# STM32F405RGT6.net
KiCad netlist of a schematic drawn in EAGLE
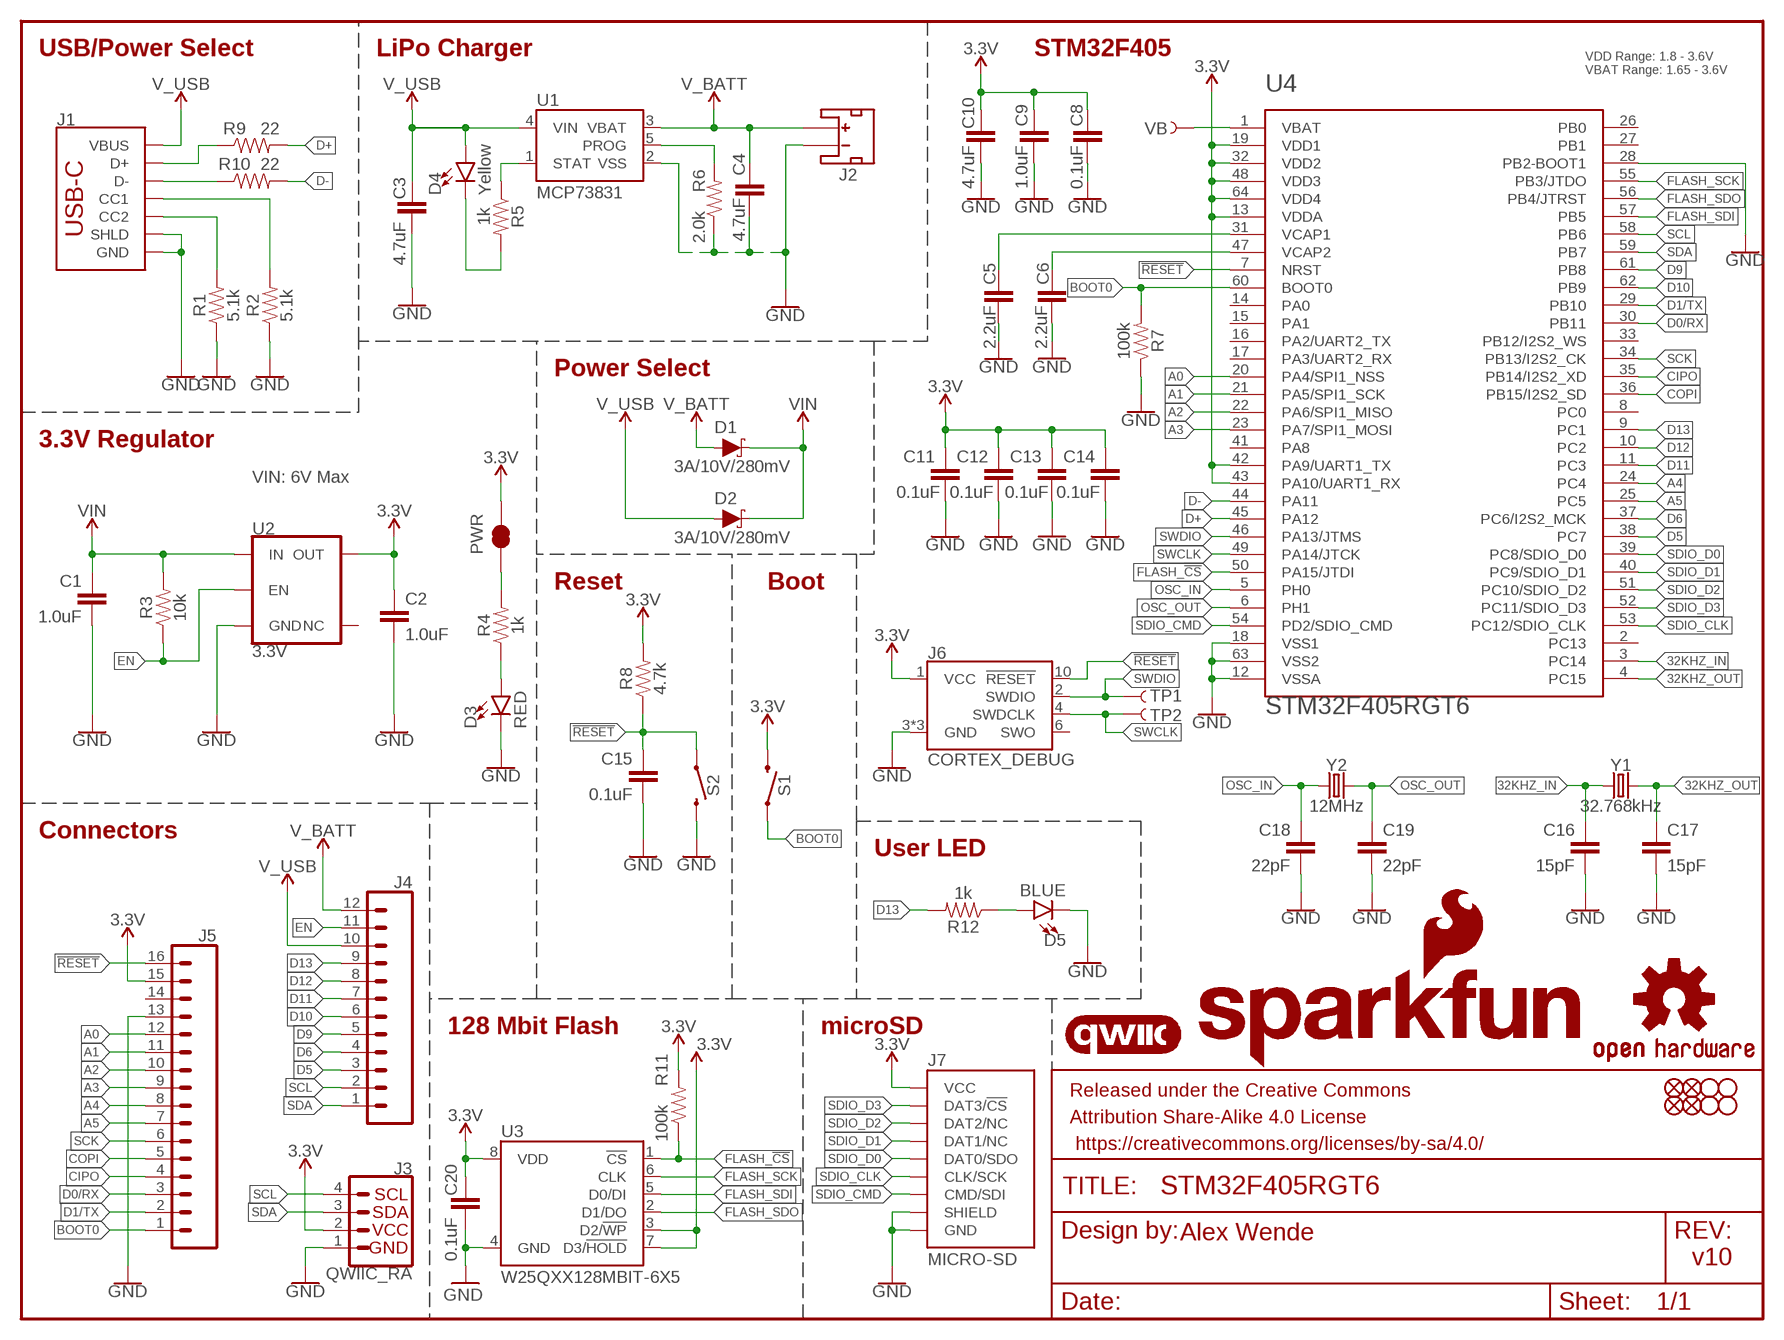
[diagram p0: schematic, sheet 1]

(export (version "E")
  (design (tool "Eeschema 10.0.6"))
  (components
    (comp (ref "C1")
      (value "1.0uF")
      (footprint "eagle-import:0402-TIGHT")
      (libsource (lib "eagle-import") (part "1.0UF-0402T-16V-10%"))
    )
    (comp (ref "C2")
      (value "1.0uF")
      (footprint "eagle-import:0402-TIGHT")
      (libsource (lib "eagle-import") (part "1.0UF-0402T-16V-10%"))
    )
    (comp (ref "C3")
      (value "4.7uF")
      (footprint "eagle-import:0402-TIGHT")
      (libsource (lib "eagle-import") (part "4.7UF-0402_TIGHT-6.3V-20%-X5R"))
    )
    (comp (ref "C4")
      (value "4.7uF")
      (footprint "eagle-import:0402-TIGHT")
      (libsource (lib "eagle-import") (part "4.7UF-0402_TIGHT-6.3V-20%-X5R"))
    )
    (comp (ref "C5")
      (value "2.2uF")
      (footprint "eagle-import:0402-TIGHT")
      (libsource (lib "eagle-import") (part "2.2UF-0402_TIGHT-10V-10%-X5R"))
    )
    (comp (ref "C6")
      (value "2.2uF")
      (footprint "eagle-import:0402-TIGHT")
      (libsource (lib "eagle-import") (part "2.2UF-0402_TIGHT-10V-10%-X5R"))
    )
    (comp (ref "C8")
      (value "0.1uF")
      (footprint "eagle-import:0402-TIGHT")
      (libsource (lib "eagle-import") (part "0.1UF-0402T-10V-10%-X7R"))
    )
    (comp (ref "C9")
      (value "1.0uF")
      (footprint "eagle-import:0402-TIGHT")
      (libsource (lib "eagle-import") (part "1.0UF-0402T-16V-10%"))
    )
    (comp (ref "C10")
      (value "4.7uF")
      (footprint "eagle-import:0402-TIGHT")
      (libsource (lib "eagle-import") (part "4.7UF-0402_TIGHT-6.3V-20%-X5R"))
    )
    (comp (ref "C11")
      (value "0.1uF")
      (footprint "eagle-import:0402-TIGHT")
      (libsource (lib "eagle-import") (part "0.1UF-0402T-10V-10%-X7R"))
    )
    (comp (ref "C12")
      (value "0.1uF")
      (footprint "eagle-import:0402-TIGHT")
      (libsource (lib "eagle-import") (part "0.1UF-0402T-10V-10%-X7R"))
    )
    (comp (ref "C13")
      (value "0.1uF")
      (footprint "eagle-import:0402-TIGHT")
      (libsource (lib "eagle-import") (part "0.1UF-0402T-10V-10%-X7R"))
    )
    (comp (ref "C14")
      (value "0.1uF")
      (footprint "eagle-import:0402-TIGHT")
      (libsource (lib "eagle-import") (part "0.1UF-0402T-10V-10%-X7R"))
    )
    (comp (ref "C15")
      (value "0.1uF")
      (footprint "eagle-import:0402-TIGHT")
      (libsource (lib "eagle-import") (part "0.1UF-0402T-10V-10%-X7R"))
    )
    (comp (ref "C16")
      (value "15pF")
      (footprint "eagle-import:0402-TIGHT")
      (libsource (lib "eagle-import") (part "15PF-0402T-50V-5%"))
    )
    (comp (ref "C17")
      (value "15pF")
      (footprint "eagle-import:0402-TIGHT")
      (libsource (lib "eagle-import") (part "15PF-0402T-50V-5%"))
    )
    (comp (ref "C18")
      (value "22pF")
      (footprint "eagle-import:0402-TIGHT")
      (libsource (lib "eagle-import") (part "22PF-0402T-16V-10%"))
    )
    (comp (ref "C19")
      (value "22pF")
      (footprint "eagle-import:0402-TIGHT")
      (libsource (lib "eagle-import") (part "22PF-0402T-16V-10%"))
    )
    (comp (ref "C20")
      (value "0.1uF")
      (footprint "eagle-import:0402-TIGHT")
      (libsource (lib "eagle-import") (part "0.1UF-0402T-10V-10%-X7R"))
    )
    (comp (ref "D1")
      (value "3A/10V/280mV")
      (footprint "eagle-import:SOD-323")
      (libsource (lib "eagle-import") (part "DIODE-SCHOTTKY-BAT60A"))
    )
    (comp (ref "D2")
      (value "3A/10V/280mV")
      (footprint "eagle-import:SOD-323")
      (libsource (lib "eagle-import") (part "DIODE-SCHOTTKY-BAT60A"))
    )
    (comp (ref "D3")
      (value "RED")
      (footprint "eagle-import:LED-0603")
      (libsource (lib "eagle-import") (part "LED-RED0603"))
    )
    (comp (ref "D4")
      (value "Yellow")
      (footprint "eagle-import:LED-0603")
      (libsource (lib "eagle-import") (part "LED-YELLOW0603"))
    )
    (comp (ref "D5")
      (value "BLUE")
      (footprint "eagle-import:LED-0603")
      (libsource (lib "eagle-import") (part "LED-BLUE0603"))
    )
    (comp (ref "FD1")
      (value "FIDUCIALUFIDUCIAL")
      (footprint "eagle-import:FIDUCIAL-MICRO")
      (libsource (lib "eagle-import") (part "FIDUCIALUFIDUCIAL"))
    )
    (comp (ref "FD2")
      (value "FIDUCIALUFIDUCIAL")
      (footprint "eagle-import:FIDUCIAL-MICRO")
      (libsource (lib "eagle-import") (part "FIDUCIALUFIDUCIAL"))
    )
    (comp (ref "FD3")
      (value "FIDUCIALUFIDUCIAL")
      (footprint "eagle-import:FIDUCIAL-MICRO")
      (libsource (lib "eagle-import") (part "FIDUCIALUFIDUCIAL"))
    )
    (comp (ref "FD4")
      (value "FIDUCIALUFIDUCIAL")
      (footprint "eagle-import:FIDUCIAL-MICRO")
      (libsource (lib "eagle-import") (part "FIDUCIALUFIDUCIAL"))
    )
    (comp (ref "FRAME1")
      (value "FRAME-LETTER")
      (footprint "eagle-import:CREATIVE_COMMONS")
      (libsource (lib "eagle-import") (part "FRAME-LETTER"))
    )
    (comp (ref "H1")
      (value "STAND-OFFTIGHT")
      (footprint "eagle-import:STAND-OFF-TIGHT")
      (libsource (lib "eagle-import") (part "STAND-OFFTIGHT"))
    )
    (comp (ref "H2")
      (value "STAND-OFFTIGHT")
      (footprint "eagle-import:STAND-OFF-TIGHT")
      (libsource (lib "eagle-import") (part "STAND-OFFTIGHT"))
    )
    (comp (ref "H3")
      (value "STAND-OFFTIGHT")
      (footprint "eagle-import:STAND-OFF-TIGHT")
      (libsource (lib "eagle-import") (part "STAND-OFFTIGHT"))
    )
    (comp (ref "H4")
      (value "STAND-OFFTIGHT")
      (footprint "eagle-import:STAND-OFF-TIGHT")
      (libsource (lib "eagle-import") (part "STAND-OFFTIGHT"))
    )
    (comp (ref "J1")
      (value "USB_C_2-LAYER_PADS")
      (footprint "eagle-import:USB-C-16P-2LAYER-PADS")
      (libsource (lib "eagle-import") (part "USB_C_2-LAYER_PADS"))
    )
    (comp (ref "J2")
      (value "JST_2MM_MALE")
      (footprint "eagle-import:JST-2-SMD")
      (libsource (lib "eagle-import") (part "JST_2MM_MALE"))
    )
    (comp (ref "J3")
      (value "QWIIC_RA")
      (footprint "eagle-import:JST04_1MM_RA")
      (libsource (lib "eagle-import") (part "QWIIC_CONNECTORJS-1MM"))
    )
    (comp (ref "J4")
      (value "CONN_12SM_SQ_NO_SILK")
      (footprint "eagle-import:1X12_SM_SQ_NOSILK")
      (libsource (lib "eagle-import") (part "CONN_12SM_SQ_NO_SILK"))
    )
    (comp (ref "J5")
      (value "CONN_161X16_SM_SQ_NOSILK")
      (footprint "eagle-import:1X16_SM_SQ_NOSILK")
      (libsource (lib "eagle-import") (part "CONN_161X16_SM_SQ_NOSILK"))
    )
    (comp (ref "J6")
      (value "CORTEX_DEBUG")
      (footprint "eagle-import:2X5-PTH-1.27MM-NO_SILK")
      (libsource (lib "eagle-import") (part "CORTEX_JTAG_DEBUG_MINIMUM_PTH_NS"))
    )
    (comp (ref "J7")
      (value "MICRO-SD")
      (footprint "eagle-import:MICRO-SD-SOCKET")
      (libsource (lib "eagle-import") (part "MICRO-SD-SDIOPUSH-PUSH"))
    )
    (comp (ref "LOGO1")
      (value "QWIIC_LOGO_5MM")
      (footprint "eagle-import:QWIIC_5MM")
      (libsource (lib "eagle-import") (part "QWIIC_LOGO_5MM"))
    )
    (comp (ref "LOGO2")
      (value "SFE_LOGO_NAME_FLAME.1_INCH")
      (footprint "eagle-import:SFE_LOGO_NAME_FLAME_.1")
      (libsource (lib "eagle-import") (part "SFE_LOGO_NAME_FLAME.1_INCH"))
    )
    (comp (ref "LOGO3")
      (value "OSHW-LOGOS")
      (footprint "eagle-import:OSHW-LOGO-S")
      (libsource (lib "eagle-import") (part "OSHW-LOGOS"))
    )
    (comp (ref "PWR")
      (value "JUMPER-SMT_2_NC_TRACE_NO-SILK")
      (footprint "eagle-import:SMT-JUMPER_2_NC_TRACE_NO-SILK")
      (libsource (lib "eagle-import") (part "JUMPER-SMT_2_NC_TRACE_NO-SILK"))
    )
    (comp (ref "R1")
      (value "5.1k")
      (footprint "eagle-import:0603")
      (libsource (lib "eagle-import") (part "5.1KOHM5.1KOHM-0603-1/10W-1%"))
    )
    (comp (ref "R2")
      (value "5.1k")
      (footprint "eagle-import:0603")
      (libsource (lib "eagle-import") (part "5.1KOHM5.1KOHM-0603-1/10W-1%"))
    )
    (comp (ref "R3")
      (value "10k")
      (footprint "eagle-import:0603")
      (libsource (lib "eagle-import") (part "10KOHM-0603-1/10W-1%"))
    )
    (comp (ref "R4")
      (value "1k")
      (footprint "eagle-import:0402-TIGHT")
      (libsource (lib "eagle-import") (part "1KOHM-0402T-1/16W-1%"))
    )
    (comp (ref "R5")
      (value "1k")
      (footprint "eagle-import:0402-TIGHT")
      (libsource (lib "eagle-import") (part "1KOHM-0402T-1/16W-1%"))
    )
    (comp (ref "R6")
      (value "2.0k")
      (footprint "eagle-import:0603")
      (libsource (lib "eagle-import") (part "2.0KOHM-0603-1/10W-5%"))
    )
    (comp (ref "R7")
      (value "100k")
      (footprint "eagle-import:0402-TIGHT")
      (libsource (lib "eagle-import") (part "100KOHM-0402T-1/16W-1%"))
    )
    (comp (ref "R8")
      (value "4.7k")
      (footprint "eagle-import:0603")
      (libsource (lib "eagle-import") (part "4.7KOHM-0603-1/10W-1%"))
    )
    (comp (ref "R9")
      (value "22")
      (footprint "eagle-import:0603")
      (libsource (lib "eagle-import") (part "22OHM-0603-1/10W-1%"))
    )
    (comp (ref "R10")
      (value "22")
      (footprint "eagle-import:0603")
      (libsource (lib "eagle-import") (part "22OHM-0603-1/10W-1%"))
    )
    (comp (ref "R11")
      (value "100k")
      (footprint "eagle-import:0402-TIGHT")
      (libsource (lib "eagle-import") (part "100KOHM-0402T-1/16W-1%"))
    )
    (comp (ref "R12")
      (value "1k")
      (footprint "eagle-import:0402-TIGHT")
      (libsource (lib "eagle-import") (part "1KOHM-0402T-1/16W-1%"))
    )
    (comp (ref "S1")
      (value "MOMENTARY-SWITCH-SPST-SMD-4.6X2.8MM")
      (footprint "eagle-import:TACTILE_SWITCH_SMD_4.6X2.8MM")
      (libsource (lib "eagle-import") (part "MOMENTARY-SWITCH-SPST-SMD-4.6X2.8MM"))
    )
    (comp (ref "S2")
      (value "MOMENTARY-SWITCH-SPST-SMD-4.6X2.8MM")
      (footprint "eagle-import:TACTILE_SWITCH_SMD_4.6X2.8MM")
      (libsource (lib "eagle-import") (part "MOMENTARY-SWITCH-SPST-SMD-4.6X2.8MM"))
    )
    (comp (ref "TP1")
      (value "TEST-POINT3")
      (footprint "eagle-import:PAD.03X.03")
      (libsource (lib "eagle-import") (part "TEST-POINT3"))
    )
    (comp (ref "TP2")
      (value "TEST-POINT3")
      (footprint "eagle-import:PAD.03X.03")
      (libsource (lib "eagle-import") (part "TEST-POINT3"))
    )
    (comp (ref "U1")
      (value "MCP73831")
      (footprint "eagle-import:SOT23-5")
      (libsource (lib "eagle-import") (part "MCP73831"))
    )
    (comp (ref "U2")
      (value "3.3V")
      (footprint "eagle-import:SOT23-5")
      (libsource (lib "eagle-import") (part "V_REG_AP2112K-3.3V"))
    )
    (comp (ref "U3")
      (value "W25QXX128MBIT-6X5")
      (footprint "eagle-import:WSON-8-6X5")
      (libsource (lib "eagle-import") (part "W25QXX128MBIT-6X5"))
    )
    (comp (ref "U4")
      (value "STM32F405RGT6")
      (footprint "eagle-import:TQFP64")
      (libsource (lib "eagle-import") (part "STM32F405RG"))
    )
    (comp (ref "VB")
      (value "TEST-POINT3")
      (footprint "eagle-import:PAD.03X.03")
      (libsource (lib "eagle-import") (part "TEST-POINT3"))
    )
    (comp (ref "Y1")
      (value "32.768kHz")
      (footprint "eagle-import:CRYSTAL-SMD-3.2X1.5MM")
      (libsource (lib "eagle-import") (part "CRYSTAL-32.768KHZSMD-3.2X1.5"))
    )
    (comp (ref "Y2")
      (value "12MHz")
      (footprint "eagle-import:CRYSTAL-SMD-5X3.2-4PAD")
      (libsource (lib "eagle-import") (part "CRYSTAL-12MHZ{dblquote}"))
    )
  )
  (nets
    (net (code "1") (name "/FLASH_~{CS}") (class "Default")
      (node (ref "R11") (pin "1") (pinfunction "1_1") (pintype "passive"))
      (node (ref "U3") (pin "1") (pinfunction "~{CS}_1") (pintype "bidirectional"))
      (node (ref "U4") (pin "50") (pinfunction "PA15/JTDI_50") (pintype "bidirectional"))
    )
    (net (code "2") (name "/~{RESET}") (class "Default")
      (node (ref "C15") (pin "1") (pinfunction "1_1") (pintype "passive"))
      (node (ref "J5") (pin "16") (pinfunction "16_16") (pintype "passive"))
      (node (ref "J6") (pin "10") (pinfunction "~{RESET}_10") (pintype "bidirectional"))
      (node (ref "R8") (pin "1") (pinfunction "1_1") (pintype "passive"))
      (node (ref "S2") (pin "1") (pinfunction "1_1") (pintype "passive"))
      (node (ref "S2") (pin "2") (pinfunction "1_2") (pintype "passive"))
      (node (ref "U4") (pin "7") (pinfunction "NRST_7") (pintype "bidirectional"))
    )
    (net (code "3") (name "3.3V") (class "Default")
      (node (ref "C10") (pin "1") (pinfunction "1_1") (pintype "passive"))
      (node (ref "C11") (pin "1") (pinfunction "1_1") (pintype "passive"))
      (node (ref "C12") (pin "1") (pinfunction "1_1") (pintype "passive"))
      (node (ref "C13") (pin "1") (pinfunction "1_1") (pintype "passive"))
      (node (ref "C14") (pin "1") (pinfunction "1_1") (pintype "passive"))
      (node (ref "C2") (pin "1") (pinfunction "1_1") (pintype "passive"))
      (node (ref "C20") (pin "1") (pinfunction "1_1") (pintype "passive"))
      (node (ref "C8") (pin "1") (pinfunction "1_1") (pintype "passive"))
      (node (ref "C9") (pin "1") (pinfunction "1_1") (pintype "passive"))
      (node (ref "J3") (pin "2") (pinfunction "2_2") (pintype "power_in"))
      (node (ref "J5") (pin "15") (pinfunction "15_15") (pintype "passive"))
      (node (ref "J6") (pin "1") (pinfunction "VCC_1") (pintype "bidirectional"))
      (node (ref "J7") (pin "VCC") (pinfunction "VCC_VCC") (pintype "bidirectional"))
      (node (ref "PWR") (pin "2") (pinfunction "2_2") (pintype "passive"))
      (node (ref "R11") (pin "2") (pinfunction "2_2") (pintype "passive"))
      (node (ref "R8") (pin "2") (pinfunction "2_2") (pintype "passive"))
      (node (ref "S1") (pin "3") (pinfunction "2_3") (pintype "passive"))
      (node (ref "S1") (pin "4") (pinfunction "2_4") (pintype "passive"))
      (node (ref "U2") (pin "5") (pinfunction "OUT_5") (pintype "passive"))
      (node (ref "U3") (pin "3") (pinfunction "D2/~{WP}_3") (pintype "bidirectional"))
      (node (ref "U3") (pin "7") (pinfunction "D3/~{HOLD}_7") (pintype "bidirectional"))
      (node (ref "U3") (pin "8") (pinfunction "VDD_8") (pintype "bidirectional"))
      (node (ref "U4") (pin "13") (pinfunction "VDDA_13") (pintype "bidirectional"))
      (node (ref "U4") (pin "19") (pinfunction "VDD1_19") (pintype "bidirectional"))
      (node (ref "U4") (pin "32") (pinfunction "VDD2_32") (pintype "bidirectional"))
      (node (ref "U4") (pin "42") (pinfunction "PA9/UART1_TX_42") (pintype "bidirectional"))
      (node (ref "U4") (pin "43") (pinfunction "PA10/UART1_RX_43") (pintype "bidirectional"))
      (node (ref "U4") (pin "48") (pinfunction "VDD3_48") (pintype "bidirectional"))
      (node (ref "U4") (pin "64") (pinfunction "VDD4_64") (pintype "bidirectional"))
    )
    (net (code "4") (name "32KHZ_IN") (class "Default")
      (node (ref "C16") (pin "1") (pinfunction "1_1") (pintype "passive"))
      (node (ref "U4") (pin "3") (pinfunction "PC14_3") (pintype "bidirectional"))
      (node (ref "Y1") (pin "P$1") (pinfunction "1_P$1") (pintype "passive"))
    )
    (net (code "5") (name "32KHZ_OUT") (class "Default")
      (node (ref "C17") (pin "1") (pinfunction "1_1") (pintype "passive"))
      (node (ref "U4") (pin "4") (pinfunction "PC15_4") (pintype "bidirectional"))
      (node (ref "Y1") (pin "P$2") (pinfunction "2_P$2") (pintype "passive"))
    )
    (net (code "6") (name "A0") (class "Default")
      (node (ref "J5") (pin "12") (pinfunction "12_12") (pintype "passive"))
      (node (ref "U4") (pin "20") (pinfunction "PA4/SPI1_NSS_20") (pintype "bidirectional"))
    )
    (net (code "7") (name "A1") (class "Default")
      (node (ref "J5") (pin "11") (pinfunction "11_11") (pintype "passive"))
      (node (ref "U4") (pin "21") (pinfunction "PA5/SPI1_SCK_21") (pintype "bidirectional"))
    )
    (net (code "8") (name "A2") (class "Default")
      (node (ref "J5") (pin "10") (pinfunction "10_10") (pintype "passive"))
      (node (ref "U4") (pin "22") (pinfunction "PA6/SPI1_MISO_22") (pintype "bidirectional"))
    )
    (net (code "9") (name "A3") (class "Default")
      (node (ref "J5") (pin "9") (pinfunction "9_9") (pintype "passive"))
      (node (ref "U4") (pin "23") (pinfunction "PA7/SPI1_MOSI_23") (pintype "bidirectional"))
    )
    (net (code "10") (name "A4") (class "Default")
      (node (ref "J5") (pin "8") (pinfunction "8_8") (pintype "passive"))
      (node (ref "U4") (pin "24") (pinfunction "PC4_24") (pintype "bidirectional"))
    )
    (net (code "11") (name "A5") (class "Default")
      (node (ref "J5") (pin "7") (pinfunction "7_7") (pintype "passive"))
      (node (ref "U4") (pin "25") (pinfunction "PC5_25") (pintype "bidirectional"))
    )
    (net (code "12") (name "BOOT0") (class "Default")
      (node (ref "J5") (pin "1") (pinfunction "1_1") (pintype "passive"))
      (node (ref "R7") (pin "2") (pinfunction "2_2") (pintype "passive"))
      (node (ref "S1") (pin "1") (pinfunction "1_1") (pintype "passive"))
      (node (ref "S1") (pin "2") (pinfunction "1_2") (pintype "passive"))
      (node (ref "U4") (pin "60") (pinfunction "BOOT0_60") (pintype "bidirectional"))
    )
    (net (code "13") (name "CIPO") (class "Default")
      (node (ref "J5") (pin "4") (pinfunction "4_4") (pintype "passive"))
      (node (ref "U4") (pin "35") (pinfunction "PB14/I2S2_XD_35") (pintype "bidirectional"))
    )
    (net (code "14") (name "COPI") (class "Default")
      (node (ref "J5") (pin "5") (pinfunction "5_5") (pintype "passive"))
      (node (ref "U4") (pin "36") (pinfunction "PB15/I2S2_SD_36") (pintype "bidirectional"))
    )
    (net (code "15") (name "D+") (class "Default")
      (node (ref "R9") (pin "2") (pinfunction "2_2") (pintype "passive"))
      (node (ref "U4") (pin "45") (pinfunction "PA12_45") (pintype "bidirectional"))
    )
    (net (code "16") (name "D-") (class "Default")
      (node (ref "R10") (pin "2") (pinfunction "2_2") (pintype "passive"))
      (node (ref "U4") (pin "44") (pinfunction "PA11_44") (pintype "bidirectional"))
    )
    (net (code "17") (name "D0{slash}RX") (class "Default")
      (node (ref "J5") (pin "3") (pinfunction "3_3") (pintype "passive"))
      (node (ref "U4") (pin "30") (pinfunction "PB11_30") (pintype "bidirectional"))
    )
    (net (code "18") (name "D1{slash}TX") (class "Default")
      (node (ref "J5") (pin "2") (pinfunction "2_2") (pintype "passive"))
      (node (ref "U4") (pin "29") (pinfunction "PB10_29") (pintype "bidirectional"))
    )
    (net (code "19") (name "D5") (class "Default")
      (node (ref "J4") (pin "3") (pinfunction "3_3") (pintype "passive"))
      (node (ref "U4") (pin "38") (pinfunction "PC7_38") (pintype "bidirectional"))
    )
    (net (code "20") (name "D6") (class "Default")
      (node (ref "J4") (pin "4") (pinfunction "4_4") (pintype "passive"))
      (node (ref "U4") (pin "37") (pinfunction "PC6/I2S2_MCK_37") (pintype "bidirectional"))
    )
    (net (code "21") (name "D9") (class "Default")
      (node (ref "J4") (pin "5") (pinfunction "5_5") (pintype "passive"))
      (node (ref "U4") (pin "61") (pinfunction "PB8_61") (pintype "bidirectional"))
    )
    (net (code "22") (name "D10") (class "Default")
      (node (ref "J4") (pin "6") (pinfunction "6_6") (pintype "passive"))
      (node (ref "U4") (pin "62") (pinfunction "PB9_62") (pintype "bidirectional"))
    )
    (net (code "23") (name "D11") (class "Default")
      (node (ref "J4") (pin "7") (pinfunction "7_7") (pintype "passive"))
      (node (ref "U4") (pin "11") (pinfunction "PC3_11") (pintype "bidirectional"))
    )
    (net (code "24") (name "D12") (class "Default")
      (node (ref "J4") (pin "8") (pinfunction "8_8") (pintype "passive"))
      (node (ref "U4") (pin "10") (pinfunction "PC2_10") (pintype "bidirectional"))
    )
    (net (code "25") (name "D13") (class "Default")
      (node (ref "J4") (pin "9") (pinfunction "9_9") (pintype "passive"))
      (node (ref "R12") (pin "2") (pinfunction "2_2") (pintype "passive"))
      (node (ref "U4") (pin "9") (pinfunction "PC1_9") (pintype "bidirectional"))
    )
    (net (code "26") (name "EN") (class "Default")
      (node (ref "J4") (pin "11") (pinfunction "11_11") (pintype "passive"))
      (node (ref "R3") (pin "1") (pinfunction "1_1") (pintype "passive"))
      (node (ref "U2") (pin "3") (pinfunction "EN_3") (pintype "input"))
    )
    (net (code "27") (name "FLASH_SCK") (class "Default")
      (node (ref "U3") (pin "6") (pinfunction "CLK_6") (pintype "bidirectional"))
      (node (ref "U4") (pin "55") (pinfunction "PB3/JTDO_55") (pintype "bidirectional"))
    )
    (net (code "28") (name "FLASH_SDI") (class "Default")
      (node (ref "U3") (pin "5") (pinfunction "D0/DI_5") (pintype "bidirectional"))
      (node (ref "U4") (pin "57") (pinfunction "PB5_57") (pintype "bidirectional"))
    )
    (net (code "29") (name "FLASH_SDO") (class "Default")
      (node (ref "U3") (pin "2") (pinfunction "D1/DO_2") (pintype "bidirectional"))
      (node (ref "U4") (pin "56") (pinfunction "PB4/JTRST_56") (pintype "bidirectional"))
    )
    (net (code "30") (name "GND") (class "Default")
      (node (ref "C1") (pin "2") (pinfunction "2_2") (pintype "passive"))
      (node (ref "C10") (pin "2") (pinfunction "2_2") (pintype "passive"))
      (node (ref "C11") (pin "2") (pinfunction "2_2") (pintype "passive"))
      (node (ref "C12") (pin "2") (pinfunction "2_2") (pintype "passive"))
      (node (ref "C13") (pin "2") (pinfunction "2_2") (pintype "passive"))
      (node (ref "C14") (pin "2") (pinfunction "2_2") (pintype "passive"))
      (node (ref "C15") (pin "2") (pinfunction "2_2") (pintype "passive"))
      (node (ref "C16") (pin "2") (pinfunction "2_2") (pintype "passive"))
      (node (ref "C17") (pin "2") (pinfunction "2_2") (pintype "passive"))
      (node (ref "C18") (pin "2") (pinfunction "2_2") (pintype "passive"))
      (node (ref "C19") (pin "2") (pinfunction "2_2") (pintype "passive"))
      (node (ref "C2") (pin "2") (pinfunction "2_2") (pintype "passive"))
      (node (ref "C20") (pin "2") (pinfunction "2_2") (pintype "passive"))
      (node (ref "C3") (pin "2") (pinfunction "2_2") (pintype "passive"))
      (node (ref "C4") (pin "2") (pinfunction "2_2") (pintype "passive"))
      (node (ref "C5") (pin "2") (pinfunction "2_2") (pintype "passive"))
      (node (ref "C6") (pin "2") (pinfunction "2_2") (pintype "passive"))
      (node (ref "C8") (pin "2") (pinfunction "2_2") (pintype "passive"))
      (node (ref "C9") (pin "2") (pinfunction "2_2") (pintype "passive"))
      (node (ref "D3") (pin "C") (pinfunction "C_C") (pintype "passive"))
      (node (ref "D5") (pin "C") (pinfunction "C_C") (pintype "passive"))
      (node (ref "J1") (pin "GND") (pinfunction "GND_GND") (pintype "bidirectional"))
      (node (ref "J1") (pin "GND2") (pinfunction "GND_GND2") (pintype "bidirectional"))
      (node (ref "J1") (pin "SHLD1") (pinfunction "SHLD_SHLD1") (pintype "bidirectional"))
      (node (ref "J1") (pin "SHLD2") (pinfunction "SHLD_SHLD2") (pintype "bidirectional"))
      (node (ref "J1") (pin "SHLD3") (pinfunction "SHLD_SHLD3") (pintype "bidirectional"))
      (node (ref "J1") (pin "SHLD4") (pinfunction "SHLD_SHLD4") (pintype "bidirectional"))
      (node (ref "J2") (pin "1") (pinfunction "-_1") (pintype "bidirectional"))
      (node (ref "J3") (pin "1") (pinfunction "1_1") (pintype "power_in"))
      (node (ref "J5") (pin "13") (pinfunction "13_13") (pintype "passive"))
      (node (ref "J6") (pin "3") (pinfunction "GND_3") (pintype "bidirectional"))
      (node (ref "J6") (pin "5") (pinfunction "GND_5") (pintype "bidirectional"))
      (node (ref "J6") (pin "9") (pinfunction "GND_9") (pintype "bidirectional"))
      (node (ref "J7") (pin "CD1") (pinfunction "SHIELD_CD1") (pintype "bidirectional"))
      (node (ref "J7") (pin "GND") (pinfunction "GND_GND") (pintype "bidirectional"))
      (node (ref "J7") (pin "GND1") (pinfunction "GND_GND1") (pintype "bidirectional"))
      (node (ref "J7") (pin "GND3") (pinfunction "GND_GND3") (pintype "bidirectional"))
      (node (ref "R1") (pin "1") (pinfunction "1_1") (pintype "passive"))
      (node (ref "R2") (pin "1") (pinfunction "1_1") (pintype "passive"))
      (node (ref "R6") (pin "1") (pinfunction "1_1") (pintype "passive"))
      (node (ref "R7") (pin "1") (pinfunction "1_1") (pintype "passive"))
      (node (ref "S2") (pin "3") (pinfunction "2_3") (pintype "passive"))
      (node (ref "S2") (pin "4") (pinfunction "2_4") (pintype "passive"))
      (node (ref "U1") (pin "2") (pinfunction "VSS_2") (pintype "power_in"))
      (node (ref "U2") (pin "2") (pinfunction "GND_2") (pintype "input"))
      (node (ref "U3") (pin "4") (pinfunction "GND_4") (pintype "bidirectional"))
      (node (ref "U4") (pin "12") (pinfunction "VSSA_12") (pintype "bidirectional"))
      (node (ref "U4") (pin "18") (pinfunction "VSS1_18") (pintype "bidirectional"))
      (node (ref "U4") (pin "28") (pinfunction "PB2-BOOT1_28") (pintype "bidirectional"))
      (node (ref "U4") (pin "63") (pinfunction "VSS2_63") (pintype "bidirectional"))
    )
    (net (code "31") (name "Net-(D3-PadA)") (class "Default")
      (node (ref "D3") (pin "A") (pinfunction "A_A") (pintype "passive"))
      (node (ref "R4") (pin "1") (pinfunction "1_1") (pintype "passive"))
    )
    (net (code "32") (name "Net-(D4-PadC)") (class "Default")
      (node (ref "D4") (pin "C") (pinfunction "C_C") (pintype "passive"))
      (node (ref "R5") (pin "2") (pinfunction "2_2") (pintype "passive"))
    )
    (net (code "33") (name "Net-(D5-PadA)") (class "Default")
      (node (ref "D5") (pin "A") (pinfunction "A_A") (pintype "passive"))
      (node (ref "R12") (pin "1") (pinfunction "1_1") (pintype "passive"))
    )
    (net (code "34") (name "Net-(J1-CC1)") (class "Default")
      (node (ref "J1") (pin "A5") (pinfunction "CC1_A5") (pintype "bidirectional"))
      (node (ref "R2") (pin "2") (pinfunction "2_2") (pintype "passive"))
    )
    (net (code "35") (name "Net-(J1-CC2)") (class "Default")
      (node (ref "J1") (pin "B5") (pinfunction "CC2_B5") (pintype "bidirectional"))
      (node (ref "R1") (pin "2") (pinfunction "2_2") (pintype "passive"))
    )
    (net (code "36") (name "Net-(J1-D+-PadA6)") (class "Default")
      (node (ref "J1") (pin "A6") (pinfunction "D+_A6") (pintype "bidirectional"))
      (node (ref "J1") (pin "B6") (pinfunction "D+_B6") (pintype "bidirectional"))
      (node (ref "R9") (pin "1") (pinfunction "1_1") (pintype "passive"))
    )
    (net (code "37") (name "Net-(J1-D--PadA7)") (class "Default")
      (node (ref "J1") (pin "A7") (pinfunction "D-_A7") (pintype "bidirectional"))
      (node (ref "J1") (pin "B7") (pinfunction "D-_B7") (pintype "bidirectional"))
      (node (ref "R10") (pin "1") (pinfunction "1_1") (pintype "passive"))
    )
    (net (code "38") (name "Net-(PWR-Pad1)") (class "Default")
      (node (ref "PWR") (pin "1") (pinfunction "1_1") (pintype "passive"))
      (node (ref "R4") (pin "2") (pinfunction "2_2") (pintype "passive"))
    )
    (net (code "39") (name "Net-(U1-PROG)") (class "Default")
      (node (ref "R6") (pin "2") (pinfunction "2_2") (pintype "passive"))
      (node (ref "U1") (pin "5") (pinfunction "PROG_5") (pintype "input"))
    )
    (net (code "40") (name "Net-(U1-STAT)") (class "Default")
      (node (ref "R5") (pin "1") (pinfunction "1_1") (pintype "passive"))
      (node (ref "U1") (pin "1") (pinfunction "STAT_1") (pintype "output"))
    )
    (net (code "41") (name "Net-(U4-VBAT)") (class "Default")
      (node (ref "U4") (pin "1") (pinfunction "VBAT_1") (pintype "bidirectional"))
      (node (ref "VB") (pin "P$1") (pinfunction "1_P$1") (pintype "bidirectional"))
    )
    (net (code "42") (name "Net-(U4-VCAP1)") (class "Default")
      (node (ref "C5") (pin "1") (pinfunction "1_1") (pintype "passive"))
      (node (ref "U4") (pin "31") (pinfunction "VCAP1_31") (pintype "bidirectional"))
    )
    (net (code "43") (name "Net-(U4-VCAP2)") (class "Default")
      (node (ref "C6") (pin "1") (pinfunction "1_1") (pintype "passive"))
      (node (ref "U4") (pin "47") (pinfunction "VCAP2_47") (pintype "bidirectional"))
    )
    (net (code "44") (name "OSC_IN") (class "Default")
      (node (ref "C18") (pin "1") (pinfunction "1_1") (pintype "passive"))
      (node (ref "U4") (pin "5") (pinfunction "PH0_5") (pintype "bidirectional"))
      (node (ref "Y2") (pin "1") (pinfunction "1_1") (pintype "passive"))
    )
    (net (code "45") (name "OSC_OUT") (class "Default")
      (node (ref "C19") (pin "1") (pinfunction "1_1") (pintype "passive"))
      (node (ref "U4") (pin "6") (pinfunction "PH1_6") (pintype "bidirectional"))
      (node (ref "Y2") (pin "3") (pinfunction "2_3") (pintype "passive"))
    )
    (net (code "46") (name "SCK") (class "Default")
      (node (ref "J5") (pin "6") (pinfunction "6_6") (pintype "passive"))
      (node (ref "U4") (pin "34") (pinfunction "PB13/I2S2_CK_34") (pintype "bidirectional"))
    )
    (net (code "47") (name "SCL") (class "Default")
      (node (ref "J3") (pin "4") (pinfunction "4_4") (pintype "passive"))
      (node (ref "J4") (pin "2") (pinfunction "2_2") (pintype "passive"))
      (node (ref "U4") (pin "58") (pinfunction "PB6_58") (pintype "bidirectional"))
    )
    (net (code "48") (name "SDA") (class "Default")
      (node (ref "J3") (pin "3") (pinfunction "3_3") (pintype "passive"))
      (node (ref "J4") (pin "1") (pinfunction "1_1") (pintype "passive"))
      (node (ref "U4") (pin "59") (pinfunction "PB7_59") (pintype "bidirectional"))
    )
    (net (code "49") (name "SDIO_CLK") (class "Default")
      (node (ref "J7") (pin "SCLK") (pinfunction "CLK/SCK_SCLK") (pintype "bidirectional"))
      (node (ref "U4") (pin "53") (pinfunction "PC12/SDIO_CLK_53") (pintype "bidirectional"))
    )
    (net (code "50") (name "SDIO_CMD") (class "Default")
      (node (ref "J7") (pin "DI/CMD") (pinfunction "CMD/SDI_DI/CMD") (pintype "bidirectional"))
      (node (ref "U4") (pin "54") (pinfunction "PD2/SDIO_CMD_54") (pintype "bidirectional"))
    )
    (net (code "51") (name "SDIO_D0") (class "Default")
      (node (ref "J7") (pin "DO/DAT0") (pinfunction "DAT0/SDO_DO/DAT0") (pintype "bidirectional"))
      (node (ref "U4") (pin "39") (pinfunction "PC8/SDIO_D0_39") (pintype "bidirectional"))
    )
    (net (code "52") (name "SDIO_D1") (class "Default")
      (node (ref "J7") (pin "DAT1") (pinfunction "DAT1/NC_DAT1") (pintype "bidirectional"))
      (node (ref "U4") (pin "40") (pinfunction "PC9/SDIO_D1_40") (pintype "bidirectional"))
    )
    (net (code "53") (name "SDIO_D2") (class "Default")
      (node (ref "J7") (pin "DAT2") (pinfunction "DAT2/NC_DAT2") (pintype "bidirectional"))
      (node (ref "U4") (pin "51") (pinfunction "PC10/SDIO_D2_51") (pintype "bidirectional"))
    )
    (net (code "54") (name "SDIO_D3") (class "Default")
      (node (ref "J7") (pin "CS/DAT3") (pinfunction "DAT3/~{CS}_CS/DAT3") (pintype "bidirectional"))
      (node (ref "U4") (pin "52") (pinfunction "PC11/SDIO_D3_52") (pintype "bidirectional"))
    )
    (net (code "55") (name "SWCLK") (class "Default")
      (node (ref "J6") (pin "4") (pinfunction "SWDCLK_4") (pintype "bidirectional"))
      (node (ref "TP2") (pin "P$1") (pinfunction "1_P$1") (pintype "bidirectional"))
      (node (ref "U4") (pin "49") (pinfunction "PA14/JTCK_49") (pintype "bidirectional"))
    )
    (net (code "56") (name "SWDIO") (class "Default")
      (node (ref "J6") (pin "2") (pinfunction "SWDIO_2") (pintype "bidirectional"))
      (node (ref "TP1") (pin "P$1") (pinfunction "1_P$1") (pintype "bidirectional"))
      (node (ref "U4") (pin "46") (pinfunction "PA13/JTMS_46") (pintype "bidirectional"))
    )
    (net (code "57") (name "VIN") (class "Default")
      (node (ref "C1") (pin "1") (pinfunction "1_1") (pintype "passive"))
      (node (ref "D1") (pin "C") (pinfunction "C_C") (pintype "passive"))
      (node (ref "D2") (pin "C") (pinfunction "C_C") (pintype "passive"))
      (node (ref "R3") (pin "2") (pinfunction "2_2") (pintype "passive"))
      (node (ref "U2") (pin "1") (pinfunction "IN_1") (pintype "input"))
    )
    (net (code "58") (name "V_BATT") (class "Default")
      (node (ref "C4") (pin "1") (pinfunction "1_1") (pintype "passive"))
      (node (ref "D1") (pin "A") (pinfunction "A_A") (pintype "passive"))
      (node (ref "J2") (pin "2") (pinfunction "+_2") (pintype "bidirectional"))
      (node (ref "J4") (pin "12") (pinfunction "12_12") (pintype "passive"))
      (node (ref "U1") (pin "3") (pinfunction "VBAT_3") (pintype "power_in"))
    )
    (net (code "59") (name "V_USB") (class "Default")
      (node (ref "C3") (pin "1") (pinfunction "1_1") (pintype "passive"))
      (node (ref "D2") (pin "A") (pinfunction "A_A") (pintype "passive"))
      (node (ref "D4") (pin "A") (pinfunction "A_A") (pintype "passive"))
      (node (ref "J1") (pin "VBUS1") (pinfunction "VBUS_VBUS1") (pintype "bidirectional"))
      (node (ref "J1") (pin "VBUS2") (pinfunction "VBUS_VBUS2") (pintype "bidirectional"))
      (node (ref "J4") (pin "10") (pinfunction "10_10") (pintype "passive"))
      (node (ref "U1") (pin "4") (pinfunction "VIN_4") (pintype "power_in"))
    )
    (net (code "60") (name "unconnected-(J2-PAD1-PadNC1)") (class "Default")
      (node (ref "J2") (pin "NC1") (pinfunction "PAD1_NC1") (pintype "bidirectional"))
    )
    (net (code "61") (name "unconnected-(J2-PAD2-PadNC2)") (class "Default")
      (node (ref "J2") (pin "NC2") (pinfunction "PAD2_NC2") (pintype "bidirectional"))
    )
    (net (code "62") (name "unconnected-(J5-Pad14)") (class "Default")
      (node (ref "J5") (pin "14") (pinfunction "14_14") (pintype "passive"))
    )
    (net (code "63") (name "unconnected-(J6-SWO-Pad6)") (class "Default")
      (node (ref "J6") (pin "6") (pinfunction "SWO_6") (pintype "bidirectional"))
    )
    (net (code "64") (name "unconnected-(U2-NC-Pad4)") (class "Default")
      (node (ref "U2") (pin "4") (pinfunction "NC_4") (pintype "no_connect"))
    )
    (net (code "65") (name "unconnected-(U4-PA0-Pad14)") (class "Default")
      (node (ref "U4") (pin "14") (pinfunction "PA0_14") (pintype "bidirectional"))
    )
    (net (code "66") (name "unconnected-(U4-PA1-Pad15)") (class "Default")
      (node (ref "U4") (pin "15") (pinfunction "PA1_15") (pintype "bidirectional"))
    )
    (net (code "67") (name "unconnected-(U4-PA2{slash}UART2_TX-Pad16)") (class "Default")
      (node (ref "U4") (pin "16") (pinfunction "PA2/UART2_TX_16") (pintype "bidirectional"))
    )
    (net (code "68") (name "unconnected-(U4-PA3{slash}UART2_RX-Pad17)") (class "Default")
      (node (ref "U4") (pin "17") (pinfunction "PA3/UART2_RX_17") (pintype "bidirectional"))
    )
    (net (code "69") (name "unconnected-(U4-PA8-Pad41)") (class "Default")
      (node (ref "U4") (pin "41") (pinfunction "PA8_41") (pintype "bidirectional"))
    )
    (net (code "70") (name "unconnected-(U4-PB0-Pad26)") (class "Default")
      (node (ref "U4") (pin "26") (pinfunction "PB0_26") (pintype "bidirectional"))
    )
    (net (code "71") (name "unconnected-(U4-PB1-Pad27)") (class "Default")
      (node (ref "U4") (pin "27") (pinfunction "PB1_27") (pintype "bidirectional"))
    )
    (net (code "72") (name "unconnected-(U4-PB12{slash}I2S2_WS-Pad33)") (class "Default")
      (node (ref "U4") (pin "33") (pinfunction "PB12/I2S2_WS_33") (pintype "bidirectional"))
    )
    (net (code "73") (name "unconnected-(U4-PC0-Pad8)") (class "Default")
      (node (ref "U4") (pin "8") (pinfunction "PC0_8") (pintype "bidirectional"))
    )
    (net (code "74") (name "unconnected-(U4-PC13-Pad2)") (class "Default")
      (node (ref "U4") (pin "2") (pinfunction "PC13_2") (pintype "bidirectional"))
    )
  )
)
